# IR2110.net
KiCad netlist of a schematic drawn in Altium Designer
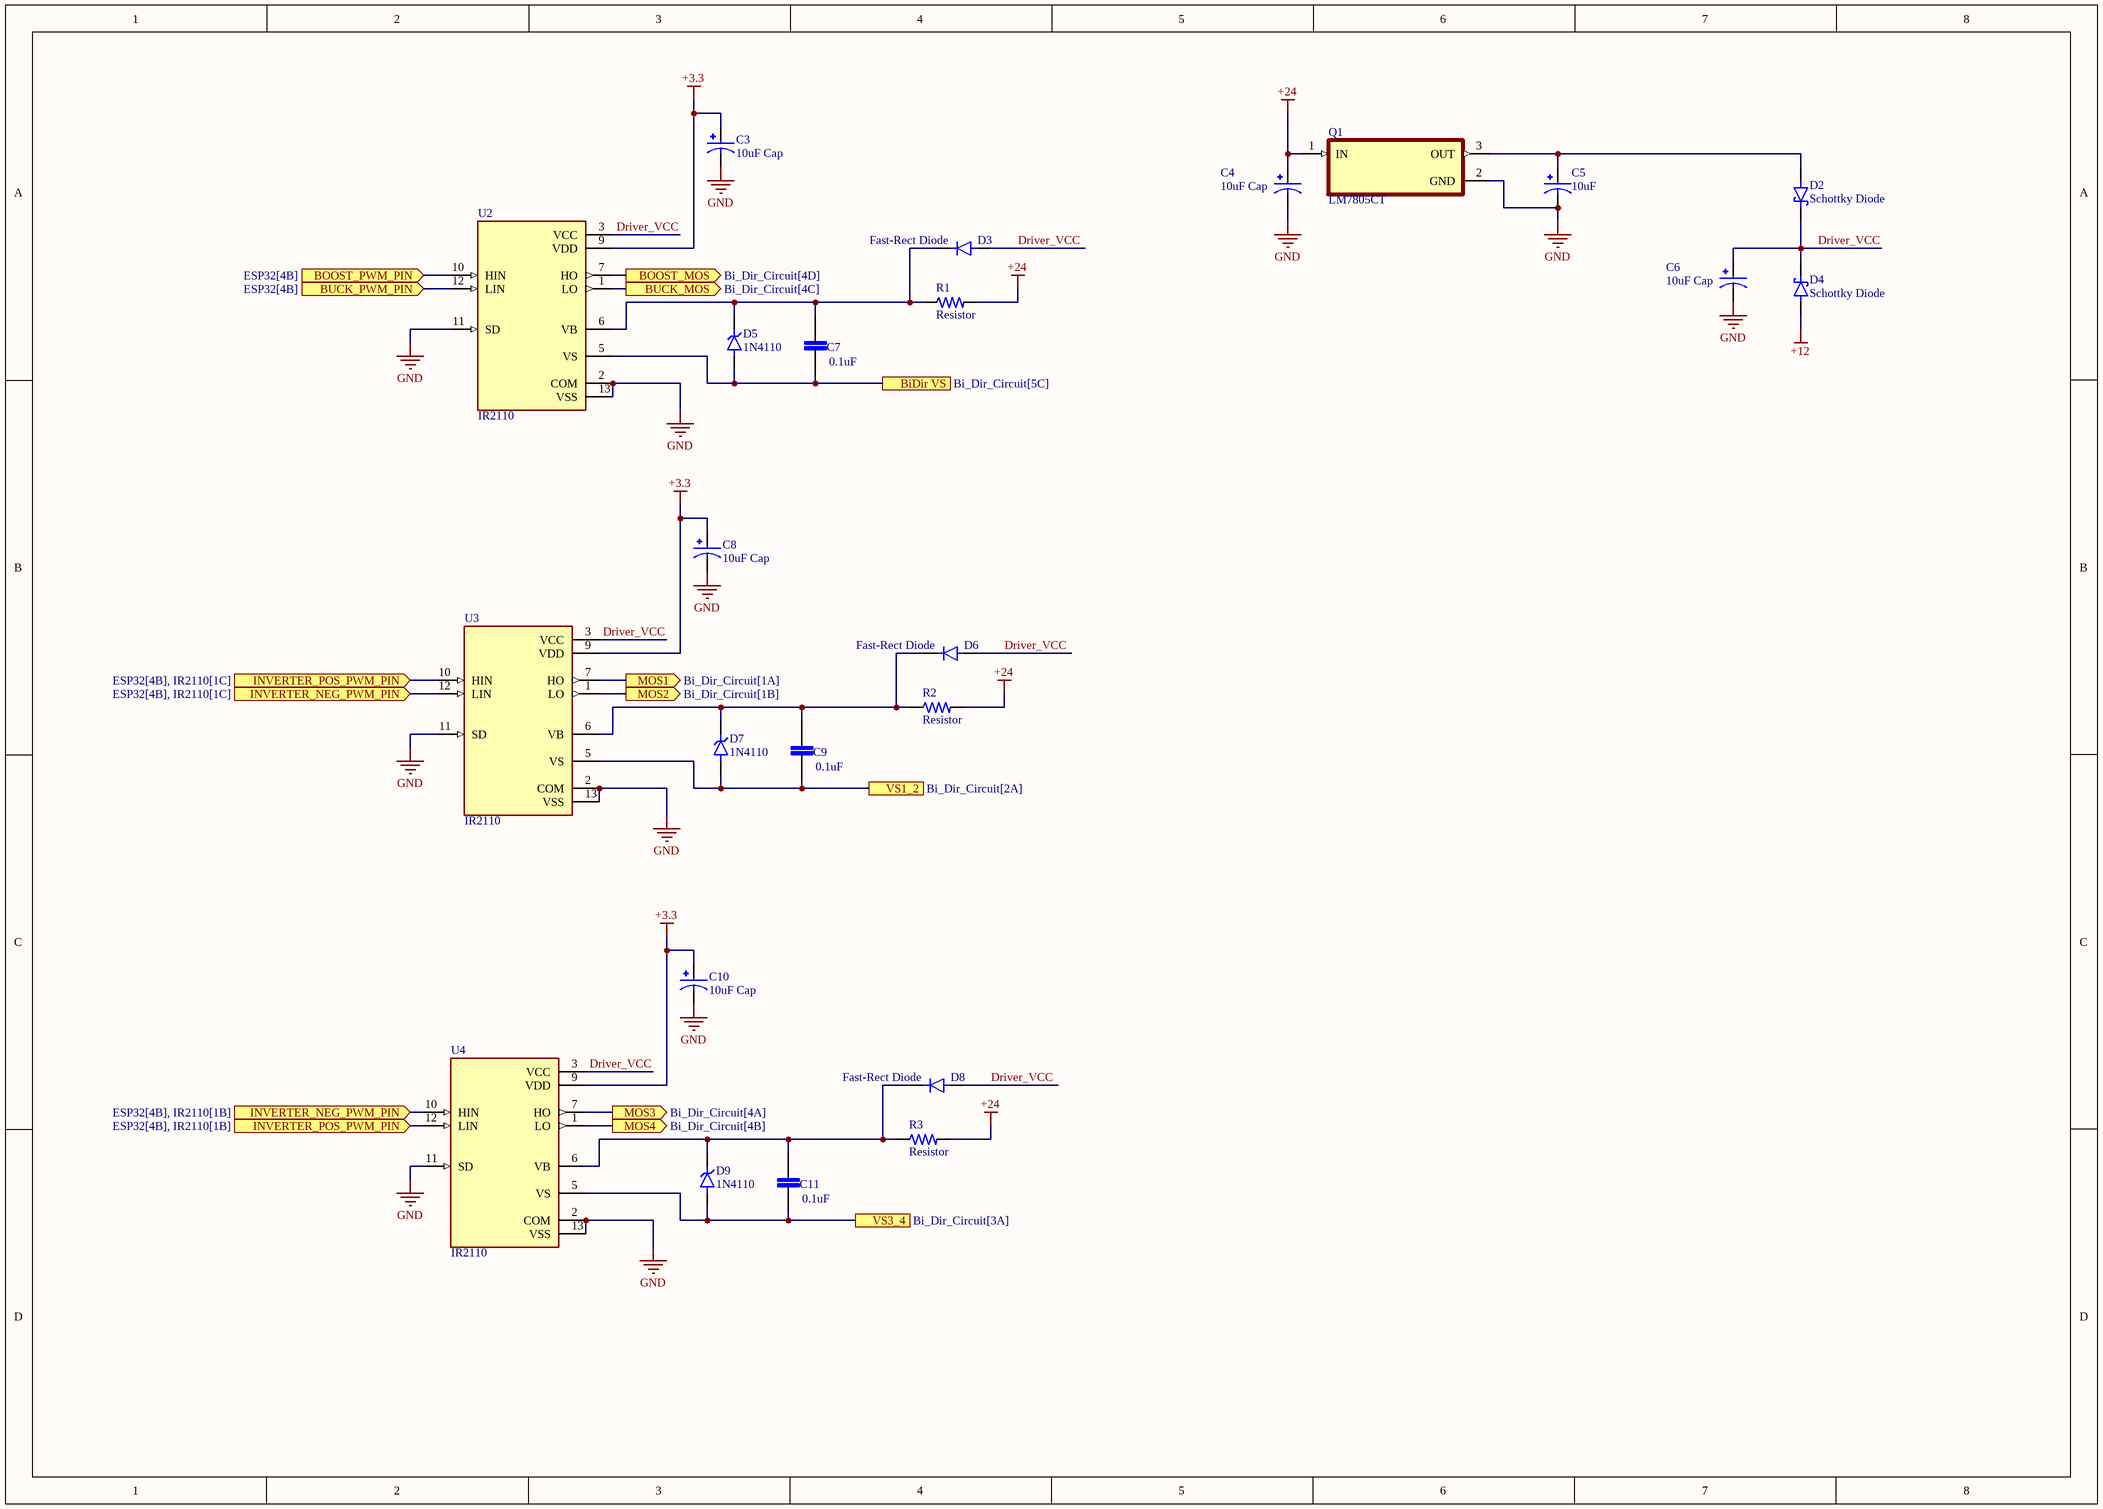
[diagram p0: IR2110.SchDoc]

(export (version "E")
  (design (tool "Eeschema 10.0.6"))
  (components
    (comp (ref "C3")
      (value "10uF Cap")
      (footprint "CAP_10uF")
      (description "CAP ALUM 10UF 20% 50V RADIAL")
      (fields (field (name "MP") "ECE-A1HN100UI") (field (name "MF") "Panasonic"))
      (libsource (lib "MySCH_Library") (part "10uF Cap"))
    )
    (comp (ref "C4")
      (value "10uF Cap")
      (footprint "CAP_10uF")
      (description "CAP ALUM 10UF 20% 50V RADIAL")
      (fields (field (name "MP") "ECE-A1HN100UI") (field (name "MF") "Panasonic"))
      (libsource (lib "MySCH_Library") (part "10uF Cap"))
    )
    (comp (ref "C5")
      (value "10uF")
      (footprint "CAP_10uF")
      (description "CAP ALUM 10UF 20% 50V RADIAL")
      (fields (field (name "MP") "ECE-A1HN100UI") (field (name "MF") "Panasonic"))
      (libsource (lib "MySCH_Library") (part "10uF Cap"))
    )
    (comp (ref "C6")
      (value "10uF Cap")
      (footprint "CAP_10uF")
      (description "CAP ALUM 10UF 20% 50V RADIAL")
      (fields (field (name "MP") "ECE-A1HN100UI") (field (name "MF") "Panasonic"))
      (libsource (lib "MySCH_Library") (part "10uF Cap"))
    )
    (comp (ref "C7")
      (value "0.1uF")
      (footprint "Ceramic Capacitor")
      (fields (field (name "MP") "LD051A121KAB2A") (field (name "MF") "AVX"))
      (libsource (lib "Capacitors Through Hole") (part "Ceramic Capacitor"))
    )
    (comp (ref "C8")
      (value "10uF Cap")
      (footprint "CAP_10uF")
      (description "CAP ALUM 10UF 20% 50V RADIAL")
      (fields (field (name "MP") "ECE-A1HN100UI") (field (name "MF") "Panasonic"))
      (libsource (lib "MySCH_Library") (part "10uF Cap"))
    )
    (comp (ref "C9")
      (value "0.1uF")
      (footprint "Ceramic Capacitor")
      (fields (field (name "MP") "LD051A121KAB2A") (field (name "MF") "AVX"))
      (libsource (lib "Capacitors Through Hole") (part "Ceramic Capacitor"))
    )
    (comp (ref "C10")
      (value "10uF Cap")
      (footprint "CAP_10uF")
      (description "CAP ALUM 10UF 20% 50V RADIAL")
      (fields (field (name "MP") "ECE-A1HN100UI") (field (name "MF") "Panasonic"))
      (libsource (lib "MySCH_Library") (part "10uF Cap"))
    )
    (comp (ref "C11")
      (value "0.1uF")
      (footprint "Ceramic Capacitor")
      (fields (field (name "MP") "LD051A121KAB2A") (field (name "MF") "AVX"))
      (libsource (lib "Capacitors Through Hole") (part "Ceramic Capacitor"))
    )
    (comp (ref "D2")
      (value "Schottky Diode")
      (footprint "Common Trhough Hole")
      (fields (field (name "MF") "Diodes Inc.") (field (name "MP") "1N5817-T"))
      (libsource (lib "Diodes Through Hole") (part "Schottky Diode"))
    )
    (comp (ref "D3")
      (value "Fast-Rect Diode")
      (footprint "Common Trhough Hole")
      (fields (field (name "MF") "NTE Electronics, Inc.") (field (name "MP") "1N4007"))
      (libsource (lib "Diodes Through Hole") (part "Normal Diode"))
    )
    (comp (ref "D4")
      (value "Schottky Diode")
      (footprint "Common Trhough Hole")
      (fields (field (name "MF") "Diodes Inc.") (field (name "MP") "1N5817-T"))
      (libsource (lib "Diodes Through Hole") (part "Schottky Diode"))
    )
    (comp (ref "D5")
      (value "1N4110")
      (footprint "Common Trhough Hole")
      (fields (field (name "MP") "1SMA5926") (field (name "MF") "Taiwan Semiconductor"))
      (libsource (lib "Diodes Through Hole") (part "Zener Diode"))
    )
    (comp (ref "D6")
      (value "Fast-Rect Diode")
      (footprint "Common Trhough Hole")
      (fields (field (name "MF") "NTE Electronics, Inc.") (field (name "MP") "1N4007"))
      (libsource (lib "Diodes Through Hole") (part "Normal Diode"))
    )
    (comp (ref "D7")
      (value "1N4110")
      (footprint "Common Trhough Hole")
      (fields (field (name "MP") "1SMA5926") (field (name "MF") "Taiwan Semiconductor"))
      (libsource (lib "Diodes Through Hole") (part "Zener Diode"))
    )
    (comp (ref "D8")
      (value "Fast-Rect Diode")
      (footprint "Common Trhough Hole")
      (fields (field (name "MF") "NTE Electronics, Inc.") (field (name "MP") "1N4007"))
      (libsource (lib "Diodes Through Hole") (part "Normal Diode"))
    )
    (comp (ref "D9")
      (value "1N4110")
      (footprint "Common Trhough Hole")
      (fields (field (name "MP") "1SMA5926") (field (name "MF") "Taiwan Semiconductor"))
      (libsource (lib "Diodes Through Hole") (part "Zener Diode"))
    )
    (comp (ref "Q1")
      (value "LM7805CT")
      (footprint "LM7805CT")
      (fields (field (name "MP") "LM7805CT/NOPB"))
      (libsource (lib "Voltage Regulators Through Hole") (part "LM7805CT"))
    )
    (comp (ref "R1")
      (value "Resistor")
      (footprint "Resistor_Through Hole")
      (fields
        (field (name "MP") "2-2176053-0")
        (field (name "TOLERANCE") "1%")
        (field (name "MF") "TE Connectivity")
      )
      (libsource (lib "Resistors Through Hole") (part "Resistor"))
    )
    (comp (ref "R2")
      (value "Resistor")
      (footprint "Resistor_Through Hole")
      (fields
        (field (name "MP") "2-2176053-0")
        (field (name "TOLERANCE") "1%")
        (field (name "MF") "TE Connectivity")
      )
      (libsource (lib "Resistors Through Hole") (part "Resistor"))
    )
    (comp (ref "R3")
      (value "Resistor")
      (footprint "Resistor_Through Hole")
      (fields
        (field (name "MP") "2-2176053-0")
        (field (name "TOLERANCE") "1%")
        (field (name "MF") "TE Connectivity")
      )
      (libsource (lib "Resistors Through Hole") (part "Resistor"))
    )
    (comp (ref "U2")
      (value "IR2110")
      (footprint "IR2110")
      (description "Half-Bridge Gate Driver IC Non-Inverting 16-SOIC")
      (fields (field (name "MF") "Infineon"))
      (libsource (lib "MySCH_Library") (part "IR2110"))
    )
    (comp (ref "U3")
      (value "IR2110")
      (footprint "IR2110")
      (description "Half-Bridge Gate Driver IC Non-Inverting 16-SOIC")
      (fields (field (name "MF") "Infineon"))
      (libsource (lib "MySCH_Library") (part "IR2110"))
    )
    (comp (ref "U4")
      (value "IR2110")
      (footprint "IR2110")
      (description "Half-Bridge Gate Driver IC Non-Inverting 16-SOIC")
      (fields (field (name "MF") "Infineon"))
      (libsource (lib "MySCH_Library") (part "IR2110"))
    )
  )
  (nets
    (net (code "1") (name "+3.3") (class "Default")
      (node (ref "C10") (pin "P") (pinfunction "P_P") (pintype "passive"))
      (node (ref "C3") (pin "P") (pinfunction "P_P") (pintype "passive"))
      (node (ref "C8") (pin "P") (pinfunction "P_P") (pintype "passive"))
      (node (ref "U2") (pin "9") (pinfunction "VDD_9") (pintype "power_in"))
      (node (ref "U3") (pin "9") (pinfunction "VDD_9") (pintype "power_in"))
      (node (ref "U4") (pin "9") (pinfunction "VDD_9") (pintype "power_in"))
    )
    (net (code "2") (name "+12") (class "Default")
      (node (ref "D4") (pin "2") (pinfunction "A_2") (pintype "passive"))
    )
    (net (code "3") (name "+24") (class "Default")
      (node (ref "C4") (pin "P") (pinfunction "P_P") (pintype "passive"))
      (node (ref "Q1") (pin "1") (pinfunction "IN_1") (pintype "input"))
      (node (ref "R1") (pin "2") (pinfunction "2_2") (pintype "passive"))
      (node (ref "R2") (pin "2") (pinfunction "2_2") (pintype "passive"))
      (node (ref "R3") (pin "2") (pinfunction "2_2") (pintype "passive"))
    )
    (net (code "4") (name "/BOOST_MOS") (class "Default")
      (node (ref "U2") (pin "7") (pinfunction "HO_7") (pintype "output"))
    )
    (net (code "5") (name "/BOOST_PWM_PIN") (class "Default")
      (node (ref "U2") (pin "10") (pinfunction "HIN_10") (pintype "input"))
    )
    (net (code "6") (name "/BUCK_MOS") (class "Default")
      (node (ref "U2") (pin "1") (pinfunction "LO_1") (pintype "output"))
    )
    (net (code "7") (name "/BUCK_PWM_PIN") (class "Default")
      (node (ref "U2") (pin "12") (pinfunction "LIN_12") (pintype "input"))
    )
    (net (code "8") (name "/BiDir VS") (class "Default")
      (node (ref "C7") (pin "1") (pinfunction "1_1") (pintype "passive"))
      (node (ref "D5") (pin "2") (pinfunction "A_2") (pintype "passive"))
      (node (ref "U2") (pin "5") (pinfunction "VS_5") (pintype "passive"))
    )
    (net (code "9") (name "/Driver_VCC") (class "Default")
      (node (ref "C6") (pin "P") (pinfunction "P_P") (pintype "passive"))
      (node (ref "D2") (pin "1") (pinfunction "K_1") (pintype "passive"))
      (node (ref "D3") (pin "2") (pinfunction "A_2") (pintype "passive"))
      (node (ref "D4") (pin "1") (pinfunction "K_1") (pintype "passive"))
      (node (ref "D6") (pin "2") (pinfunction "A_2") (pintype "passive"))
      (node (ref "D8") (pin "2") (pinfunction "A_2") (pintype "passive"))
      (node (ref "U2") (pin "3") (pinfunction "VCC_3") (pintype "power_in"))
      (node (ref "U3") (pin "3") (pinfunction "VCC_3") (pintype "power_in"))
      (node (ref "U4") (pin "3") (pinfunction "VCC_3") (pintype "power_in"))
    )
    (net (code "10") (name "/INVERTER_NEG_PWM_PIN") (class "Default")
      (node (ref "U3") (pin "12") (pinfunction "LIN_12") (pintype "input"))
      (node (ref "U4") (pin "10") (pinfunction "HIN_10") (pintype "input"))
    )
    (net (code "11") (name "/INVERTER_POS_PWM_PIN") (class "Default")
      (node (ref "U3") (pin "10") (pinfunction "HIN_10") (pintype "input"))
      (node (ref "U4") (pin "12") (pinfunction "LIN_12") (pintype "input"))
    )
    (net (code "12") (name "/MOS1") (class "Default")
      (node (ref "U3") (pin "7") (pinfunction "HO_7") (pintype "output"))
    )
    (net (code "13") (name "/MOS2") (class "Default")
      (node (ref "U3") (pin "1") (pinfunction "LO_1") (pintype "output"))
    )
    (net (code "14") (name "/MOS3") (class "Default")
      (node (ref "U4") (pin "7") (pinfunction "HO_7") (pintype "output"))
    )
    (net (code "15") (name "/MOS4") (class "Default")
      (node (ref "U4") (pin "1") (pinfunction "LO_1") (pintype "output"))
    )
    (net (code "16") (name "/VS1_2") (class "Default")
      (node (ref "C9") (pin "1") (pinfunction "1_1") (pintype "passive"))
      (node (ref "D7") (pin "2") (pinfunction "A_2") (pintype "passive"))
      (node (ref "U3") (pin "5") (pinfunction "VS_5") (pintype "passive"))
    )
    (net (code "17") (name "/VS3_4") (class "Default")
      (node (ref "C11") (pin "1") (pinfunction "1_1") (pintype "passive"))
      (node (ref "D9") (pin "2") (pinfunction "A_2") (pintype "passive"))
      (node (ref "U4") (pin "5") (pinfunction "VS_5") (pintype "passive"))
    )
    (net (code "18") (name "GND") (class "Default")
      (node (ref "C10") (pin "N") (pinfunction "N_N") (pintype "passive"))
      (node (ref "C3") (pin "N") (pinfunction "N_N") (pintype "passive"))
      (node (ref "C4") (pin "N") (pinfunction "N_N") (pintype "passive"))
      (node (ref "C5") (pin "N") (pinfunction "N_N") (pintype "passive"))
      (node (ref "C6") (pin "N") (pinfunction "N_N") (pintype "passive"))
      (node (ref "C8") (pin "N") (pinfunction "N_N") (pintype "passive"))
      (node (ref "Q1") (pin "2") (pinfunction "GND_2") (pintype "power_in"))
      (node (ref "U2") (pin "11") (pinfunction "SD_11") (pintype "input"))
      (node (ref "U2") (pin "13") (pinfunction "VSS_13") (pintype "power_in"))
      (node (ref "U2") (pin "2") (pinfunction "COM_2") (pintype "power_in"))
      (node (ref "U3") (pin "11") (pinfunction "SD_11") (pintype "input"))
      (node (ref "U3") (pin "13") (pinfunction "VSS_13") (pintype "power_in"))
      (node (ref "U3") (pin "2") (pinfunction "COM_2") (pintype "power_in"))
      (node (ref "U4") (pin "11") (pinfunction "SD_11") (pintype "input"))
      (node (ref "U4") (pin "13") (pinfunction "VSS_13") (pintype "power_in"))
      (node (ref "U4") (pin "2") (pinfunction "COM_2") (pintype "power_in"))
    )
    (net (code "19") (name "Net-(D2-A)") (class "Default")
      (node (ref "C5") (pin "P") (pinfunction "P_P") (pintype "passive"))
      (node (ref "D2") (pin "2") (pinfunction "A_2") (pintype "passive"))
      (node (ref "Q1") (pin "3") (pinfunction "OUT_3") (pintype "output"))
    )
    (net (code "20") (name "Net-(D3-K)") (class "Default")
      (node (ref "C7") (pin "2") (pinfunction "2_2") (pintype "passive"))
      (node (ref "D3") (pin "1") (pinfunction "K_1") (pintype "passive"))
      (node (ref "D5") (pin "1") (pinfunction "K_1") (pintype "passive"))
      (node (ref "R1") (pin "1") (pinfunction "1_1") (pintype "passive"))
      (node (ref "U2") (pin "6") (pinfunction "VB_6") (pintype "passive"))
    )
    (net (code "21") (name "Net-(D6-K)") (class "Default")
      (node (ref "C9") (pin "2") (pinfunction "2_2") (pintype "passive"))
      (node (ref "D6") (pin "1") (pinfunction "K_1") (pintype "passive"))
      (node (ref "D7") (pin "1") (pinfunction "K_1") (pintype "passive"))
      (node (ref "R2") (pin "1") (pinfunction "1_1") (pintype "passive"))
      (node (ref "U3") (pin "6") (pinfunction "VB_6") (pintype "passive"))
    )
    (net (code "22") (name "Net-(D8-K)") (class "Default")
      (node (ref "C11") (pin "2") (pinfunction "2_2") (pintype "passive"))
      (node (ref "D8") (pin "1") (pinfunction "K_1") (pintype "passive"))
      (node (ref "D9") (pin "1") (pinfunction "K_1") (pintype "passive"))
      (node (ref "R3") (pin "1") (pinfunction "1_1") (pintype "passive"))
      (node (ref "U4") (pin "6") (pinfunction "VB_6") (pintype "passive"))
    )
  )
)
